# NL_Sheet1.net
KiCad netlist of a schematic drawn in Altium Designer
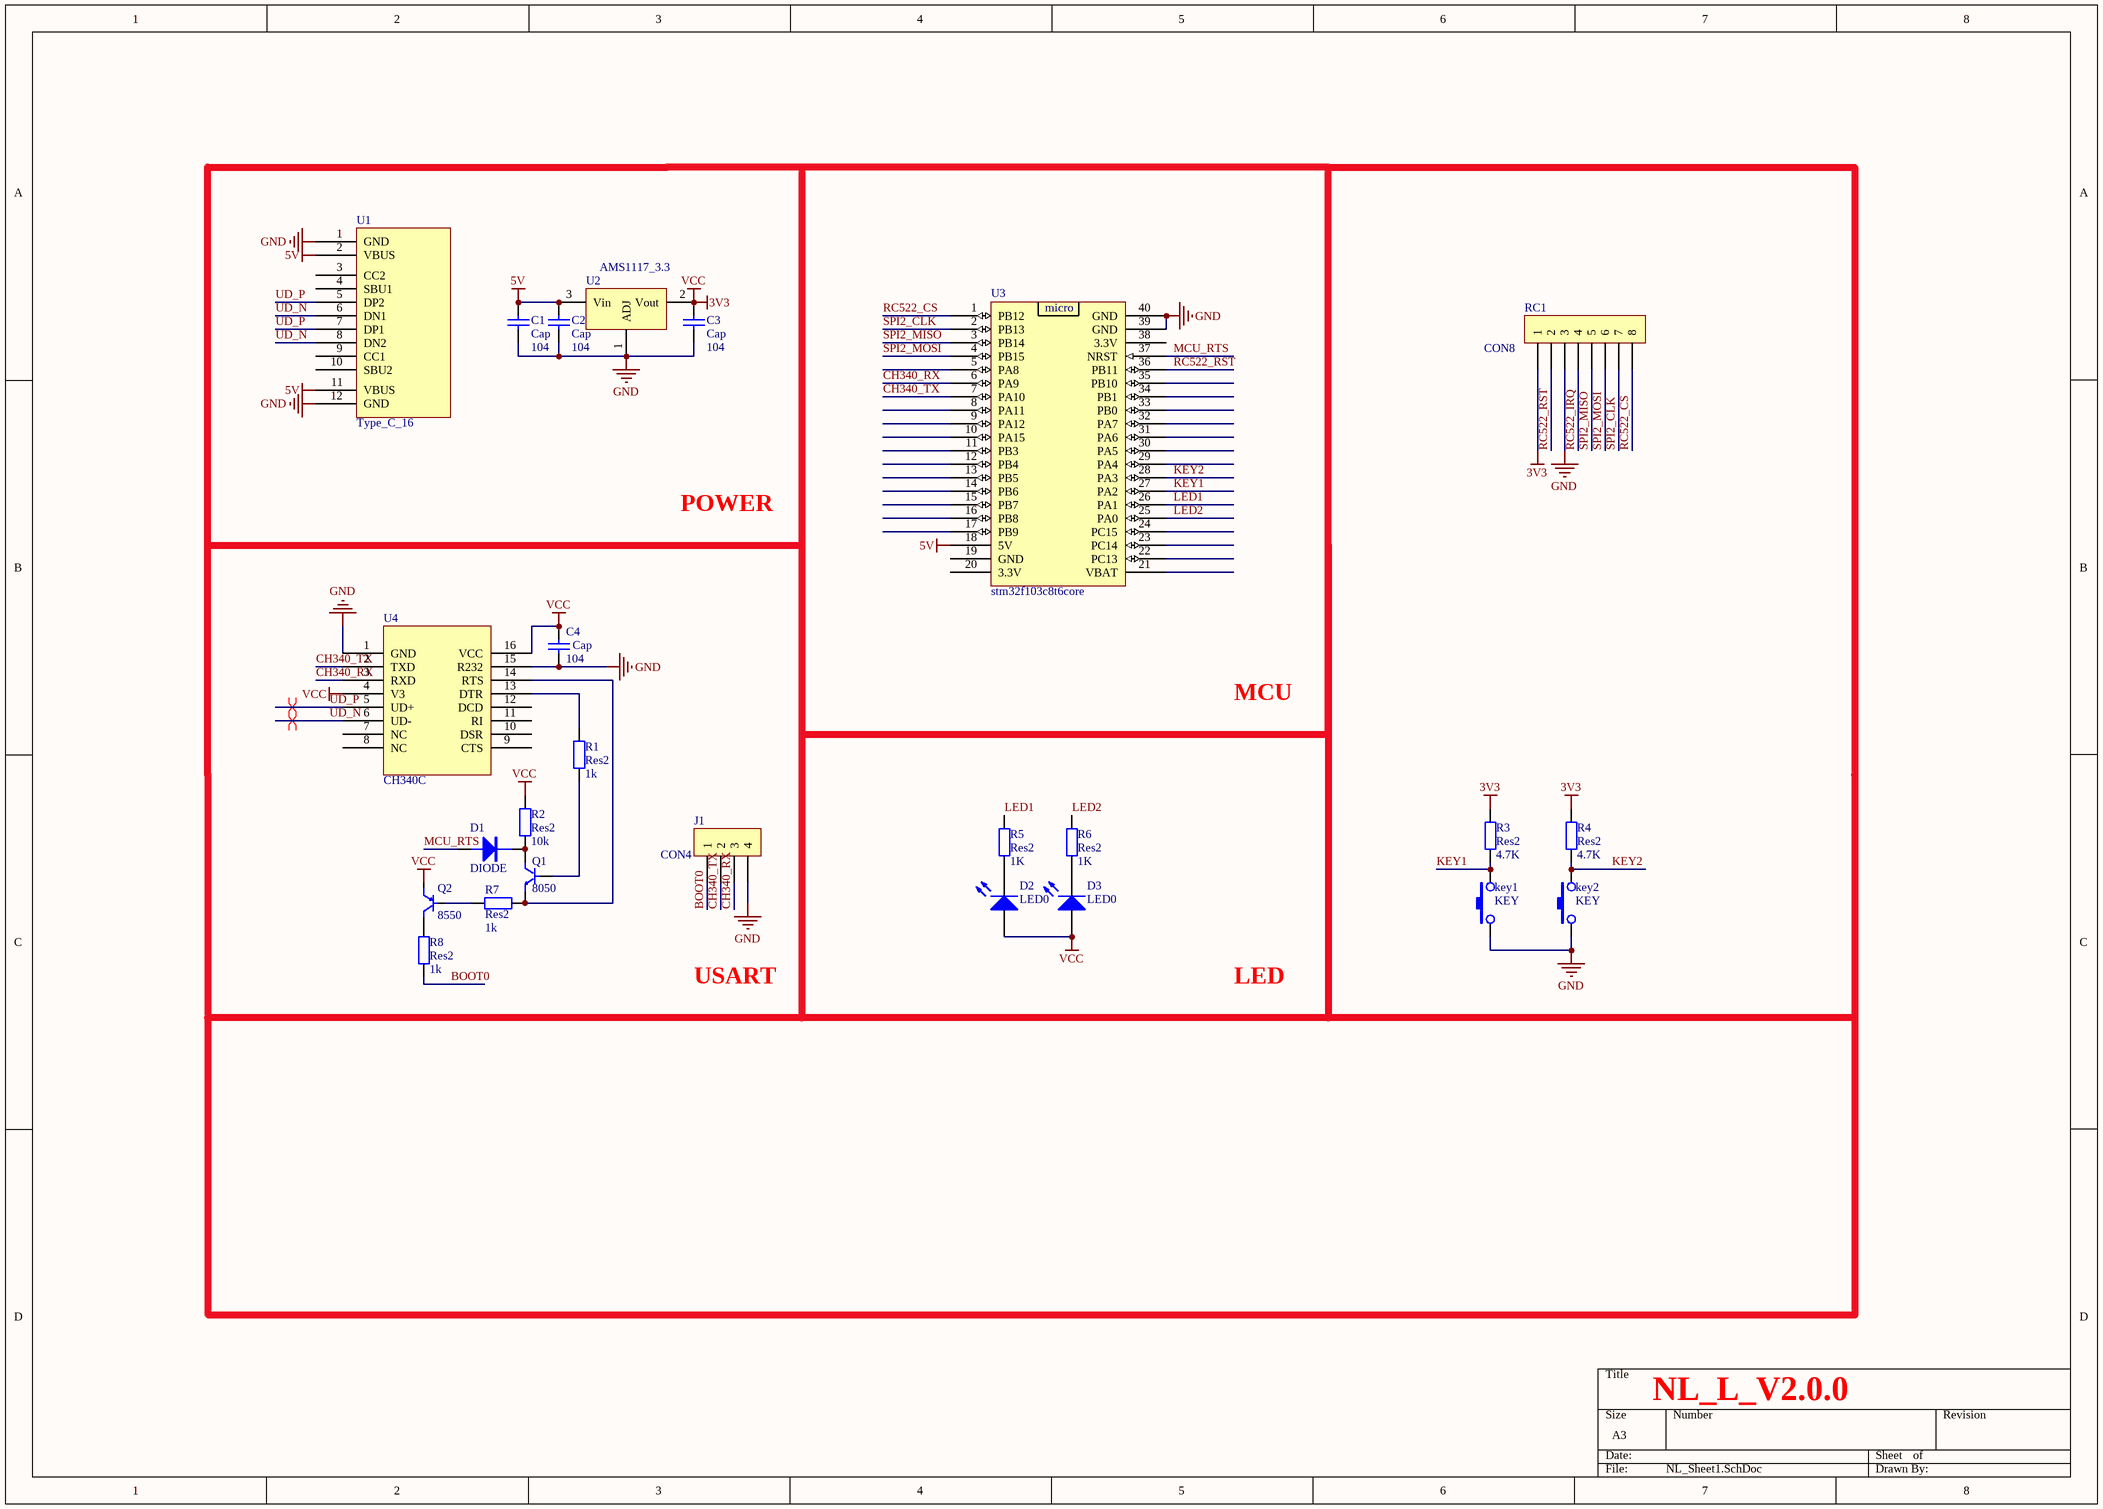
[diagram p0: NL_Sheet1.SchDoc]

(export (version "E")
  (design (tool "Eeschema 10.0.6"))
  (components
    (comp (ref "C1")
      (value "Cap")
      (footprint "0805")
      (description "Capacitor")
      (fields (field (name "ALTIUM_VALUE") "104") (field (name "PUBLISHER") "Altium Limited"))
      (libsource (lib "Miscellaneous Devices") (part "Cap"))
    )
    (comp (ref "C2")
      (value "Cap")
      (footprint "0805")
      (description "Capacitor")
      (fields (field (name "ALTIUM_VALUE") "104") (field (name "PUBLISHER") "Altium Limited"))
      (libsource (lib "Miscellaneous Devices") (part "Cap"))
    )
    (comp (ref "C3")
      (value "Cap")
      (footprint "0805")
      (description "Capacitor")
      (fields (field (name "ALTIUM_VALUE") "104") (field (name "PUBLISHER") "Altium Limited"))
      (libsource (lib "Miscellaneous Devices") (part "Cap"))
    )
    (comp (ref "C4")
      (value "Cap")
      (footprint "0805")
      (description "Capacitor")
      (fields (field (name "ALTIUM_VALUE") "104") (field (name "PUBLISHER") "Altium Limited"))
      (libsource (lib "Miscellaneous Devices") (part "Cap"))
    )
    (comp (ref "D1") (value "DIODE") (footprint "0805L") (libsource (lib "常用1") (part "DIODE")))
    (comp (ref "D2")
      (value "LED0")
      (footprint "0805")
      (description "Typical INFRARED GaAs LED")
      (fields (field (name "PUBLISHER") "Altium Limited"))
      (libsource (lib "Miscellaneous Devices") (part "LED0"))
    )
    (comp (ref "D3")
      (value "LED0")
      (footprint "0805")
      (description "Typical INFRARED GaAs LED")
      (fields (field (name "PUBLISHER") "Altium Limited"))
      (libsource (lib "Miscellaneous Devices") (part "LED0"))
    )
    (comp (ref "J1") (value "CON4") (footprint "SIP4") (libsource (lib "常用元件库") (part "CON4")))
    (comp (ref "key1") (value "KEY") (footprint "Key") (libsource (lib "常用元件库") (part "KEY")))
    (comp (ref "key2") (value "KEY") (footprint "Key") (libsource (lib "常用元件库") (part "KEY")))
    (comp (ref "Q1") (value "8050") (footprint "SOT23") (libsource (lib "NL_PCB_Project") (part "NPN")))
    (comp (ref "Q2") (value "8550") (footprint "SOT23") (libsource (lib "NL_PCB_Project") (part "PNP")))
    (comp (ref "R1")
      (value "Res2")
      (footprint "0805")
      (description "Resistor")
      (fields (field (name "ALTIUM_VALUE") "1k") (field (name "PUBLISHER") "Altium Limited"))
      (libsource (lib "Miscellaneous Devices") (part "Res2"))
    )
    (comp (ref "R2")
      (value "Res2")
      (footprint "0805")
      (description "Resistor")
      (fields (field (name "ALTIUM_VALUE") "10k") (field (name "PUBLISHER") "Altium Limited"))
      (libsource (lib "Miscellaneous Devices") (part "Res2"))
    )
    (comp (ref "R3")
      (value "Res2")
      (footprint "0805")
      (description "Resistor")
      (fields (field (name "ALTIUM_VALUE") "4.7K") (field (name "PUBLISHER") "Altium Limited"))
      (libsource (lib "Miscellaneous Devices") (part "Res2"))
    )
    (comp (ref "R4")
      (value "Res2")
      (footprint "0805")
      (description "Resistor")
      (fields (field (name "ALTIUM_VALUE") "4.7K") (field (name "PUBLISHER") "Altium Limited"))
      (libsource (lib "") (part "Res2_1"))
    )
    (comp (ref "R5")
      (value "Res2")
      (footprint "0805")
      (description "Resistor")
      (fields (field (name "ALTIUM_VALUE") "1K") (field (name "PUBLISHER") "Altium Limited"))
      (libsource (lib "") (part "Res2_1"))
    )
    (comp (ref "R6")
      (value "Res2")
      (footprint "0805")
      (description "Resistor")
      (fields (field (name "ALTIUM_VALUE") "1K") (field (name "PUBLISHER") "Altium Limited"))
      (libsource (lib "") (part "Res2_1"))
    )
    (comp (ref "R7")
      (value "Res2")
      (footprint "0805")
      (description "Resistor")
      (fields (field (name "ALTIUM_VALUE") "1k") (field (name "PUBLISHER") "Altium Limited"))
      (libsource (lib "") (part "Res2_2"))
    )
    (comp (ref "R8")
      (value "Res2")
      (footprint "0805")
      (description "Resistor")
      (fields (field (name "ALTIUM_VALUE") "1k") (field (name "PUBLISHER") "Altium Limited"))
      (libsource (lib "") (part "Res2_1"))
    )
    (comp (ref "RC1") (value "CON8") (footprint "RC522_SIP8") (libsource (lib "常用元件库") (part "CON8")))
    (comp (ref "U1") (value "Type_C_16") (footprint "Type_C16") (libsource (lib "常用1") (part "Type_C_16")))
    (comp (ref "U2")
      (value "AMS1117_3.3")
      (footprint "SOT-223")
      (description "3-Terminal Adjustable Positive Voltage Regulator")
      (libsource (lib "稳压器件") (part "LM317"))
    )
    (comp (ref "U3")
      (value "stm32f103c8t6core")
      (footprint "stm32f103DIP40")
      (libsource (lib "常用元件库") (part "stm32f103c8t6core"))
    )
    (comp (ref "U4") (value "CH340C") (footprint "SOP16") (libsource (lib "常用1") (part "CH340C")))
  )
  (nets
    (net (code "1") (name "/BOOT0") (class "Default")
      (node (ref "J1") (pin "1") (pinfunction "1_1") (pintype "passive"))
      (node (ref "R8") (pin "1") (pinfunction "1_1") (pintype "passive"))
    )
    (net (code "2") (name "/CH340_RX") (class "Default")
      (node (ref "J1") (pin "3") (pinfunction "3_3") (pintype "passive"))
      (node (ref "U3") (pin "6") (pinfunction "PA9_6") (pintype "bidirectional"))
      (node (ref "U4") (pin "3") (pinfunction "RXD_3") (pintype "passive"))
    )
    (net (code "3") (name "/CH340_TX") (class "Default")
      (node (ref "J1") (pin "2") (pinfunction "2_2") (pintype "passive"))
      (node (ref "U3") (pin "7") (pinfunction "PA10_7") (pintype "bidirectional"))
      (node (ref "U4") (pin "2") (pinfunction "TXD_2") (pintype "passive"))
    )
    (net (code "4") (name "/KEY1") (class "Default")
      (node (ref "R3") (pin "2") (pinfunction "2_2") (pintype "passive"))
      (node (ref "U3") (pin "27") (pinfunction "PA2_27") (pintype "bidirectional"))
      (node (ref "key1") (pin "2") (pinfunction "2_2") (pintype "passive"))
    )
    (net (code "5") (name "/KEY2") (class "Default")
      (node (ref "R4") (pin "1") (pinfunction "1_1") (pintype "passive"))
      (node (ref "U3") (pin "28") (pinfunction "PA3_28") (pintype "bidirectional"))
      (node (ref "key2") (pin "2") (pinfunction "2_2") (pintype "passive"))
    )
    (net (code "6") (name "/LED1") (class "Default")
      (node (ref "R5") (pin "2") (pinfunction "2_2") (pintype "passive"))
      (node (ref "U3") (pin "26") (pinfunction "PA1_26") (pintype "bidirectional"))
    )
    (net (code "7") (name "/LED2") (class "Default")
      (node (ref "R6") (pin "2") (pinfunction "2_2") (pintype "passive"))
      (node (ref "U3") (pin "25") (pinfunction "PA0_25") (pintype "bidirectional"))
    )
    (net (code "8") (name "/MCU_RTS") (class "Default")
      (node (ref "D1") (pin "1") (pintype "passive"))
      (node (ref "U3") (pin "37") (pinfunction "NRST_37") (pintype "input"))
    )
    (net (code "9") (name "/RC522_CS") (class "Default")
      (node (ref "RC1") (pin "8") (pinfunction "8_8") (pintype "passive"))
      (node (ref "U3") (pin "1") (pinfunction "PB12_1") (pintype "bidirectional"))
    )
    (net (code "10") (name "/RC522_IRQ") (class "Default")
      (node (ref "RC1") (pin "4") (pinfunction "4_4") (pintype "passive"))
    )
    (net (code "11") (name "/RC522_RST") (class "Default")
      (node (ref "RC1") (pin "2") (pinfunction "2_2") (pintype "passive"))
      (node (ref "U3") (pin "36") (pinfunction "PB11_36") (pintype "bidirectional"))
    )
    (net (code "12") (name "/SPI2_CLK") (class "Default")
      (node (ref "RC1") (pin "7") (pinfunction "7_7") (pintype "passive"))
      (node (ref "U3") (pin "2") (pinfunction "PB13_2") (pintype "bidirectional"))
    )
    (net (code "13") (name "/SPI2_MISO") (class "Default")
      (node (ref "RC1") (pin "5") (pinfunction "5_5") (pintype "passive"))
      (node (ref "U3") (pin "3") (pinfunction "PB14_3") (pintype "bidirectional"))
    )
    (net (code "14") (name "/SPI2_MOSI") (class "Default")
      (node (ref "RC1") (pin "6") (pinfunction "6_6") (pintype "passive"))
      (node (ref "U3") (pin "4") (pinfunction "PB15_4") (pintype "bidirectional"))
    )
    (net (code "15") (name "/UD_N") (class "Default")
      (node (ref "U1") (pin "6") (pinfunction "DN1_6") (pintype "passive"))
      (node (ref "U1") (pin "8") (pinfunction "DN2_8") (pintype "passive"))
      (node (ref "U4") (pin "6") (pinfunction "UD-_6") (pintype "passive"))
    )
    (net (code "16") (name "/UD_P") (class "Default")
      (node (ref "U1") (pin "5") (pinfunction "DP2_5") (pintype "passive"))
      (node (ref "U1") (pin "7") (pinfunction "DP1_7") (pintype "passive"))
      (node (ref "U4") (pin "5") (pinfunction "UD+_5") (pintype "passive"))
    )
    (net (code "17") (name "3V3") (class "Default")
      (node (ref "C3") (pin "2") (pinfunction "2_2") (pintype "passive"))
      (node (ref "C4") (pin "2") (pinfunction "2_2") (pintype "passive"))
      (node (ref "D2") (pin "1") (pinfunction "A_1") (pintype "passive"))
      (node (ref "D3") (pin "1") (pinfunction "A_1") (pintype "passive"))
      (node (ref "Q2") (pin "e") (pinfunction "e_e") (pintype "passive"))
      (node (ref "R2") (pin "1") (pinfunction "1_1") (pintype "passive"))
      (node (ref "R3") (pin "1") (pinfunction "1_1") (pintype "passive"))
      (node (ref "R4") (pin "2") (pinfunction "2_2") (pintype "passive"))
      (node (ref "RC1") (pin "1") (pinfunction "1_1") (pintype "passive"))
      (node (ref "U2") (pin "2") (pinfunction "Vout_2") (pintype "passive"))
      (node (ref "U4") (pin "16") (pinfunction "VCC_16") (pintype "passive"))
      (node (ref "U4") (pin "4") (pinfunction "V3_4") (pintype "passive"))
    )
    (net (code "18") (name "5V") (class "Default")
      (node (ref "C1") (pin "2") (pinfunction "2_2") (pintype "passive"))
      (node (ref "C2") (pin "2") (pinfunction "2_2") (pintype "passive"))
      (node (ref "U1") (pin "11") (pinfunction "VBUS_11") (pintype "passive"))
      (node (ref "U1") (pin "2") (pinfunction "VBUS_2") (pintype "passive"))
      (node (ref "U2") (pin "3") (pinfunction "Vin_3") (pintype "passive"))
      (node (ref "U3") (pin "18") (pinfunction "5V_18") (pintype "power_in"))
    )
    (net (code "19") (name "GND") (class "Default")
      (node (ref "C1") (pin "1") (pinfunction "1_1") (pintype "passive"))
      (node (ref "C2") (pin "1") (pinfunction "1_1") (pintype "passive"))
      (node (ref "C3") (pin "1") (pinfunction "1_1") (pintype "passive"))
      (node (ref "C4") (pin "1") (pinfunction "1_1") (pintype "passive"))
      (node (ref "J1") (pin "4") (pinfunction "4_4") (pintype "passive"))
      (node (ref "RC1") (pin "3") (pinfunction "3_3") (pintype "passive"))
      (node (ref "U1") (pin "1") (pinfunction "GND_1") (pintype "passive"))
      (node (ref "U1") (pin "12") (pinfunction "GND_12") (pintype "passive"))
      (node (ref "U2") (pin "1") (pinfunction "ADJ_1") (pintype "passive"))
      (node (ref "U3") (pin "39") (pinfunction "GND_39") (pintype "power_in"))
      (node (ref "U3") (pin "40") (pinfunction "GND_40") (pintype "power_in"))
      (node (ref "U4") (pin "1") (pinfunction "GND_1") (pintype "passive"))
      (node (ref "U4") (pin "15") (pinfunction "R232_15") (pintype "passive"))
      (node (ref "key1") (pin "1") (pinfunction "1_1") (pintype "passive"))
      (node (ref "key2") (pin "1") (pinfunction "1_1") (pintype "passive"))
    )
    (net (code "20") (name "Net-(D1-Pad2)") (class "Default")
      (node (ref "D1") (pin "2") (pintype "passive"))
      (node (ref "Q1") (pin "c") (pinfunction "c_c") (pintype "passive"))
      (node (ref "R2") (pin "2") (pinfunction "2_2") (pintype "passive"))
    )
    (net (code "21") (name "Net-(D2-K)") (class "Default")
      (node (ref "D2") (pin "2") (pinfunction "K_2") (pintype "passive"))
      (node (ref "R5") (pin "1") (pinfunction "1_1") (pintype "passive"))
    )
    (net (code "22") (name "Net-(D3-K)") (class "Default")
      (node (ref "D3") (pin "2") (pinfunction "K_2") (pintype "passive"))
      (node (ref "R6") (pin "1") (pinfunction "1_1") (pintype "passive"))
    )
    (net (code "23") (name "Net-(Q1-Padb)") (class "Default")
      (node (ref "Q1") (pin "b") (pinfunction "b_b") (pintype "passive"))
      (node (ref "R1") (pin "2") (pinfunction "2_2") (pintype "passive"))
    )
    (net (code "24") (name "Net-(Q2-Padb)") (class "Default")
      (node (ref "Q2") (pin "b") (pinfunction "b_b") (pintype "passive"))
      (node (ref "R7") (pin "1") (pinfunction "1_1") (pintype "passive"))
    )
    (net (code "25") (name "Net-(Q2-Padc)") (class "Default")
      (node (ref "Q2") (pin "c") (pinfunction "c_c") (pintype "passive"))
      (node (ref "R8") (pin "2") (pinfunction "2_2") (pintype "passive"))
    )
    (net (code "26") (name "Net-(U4-DTR)") (class "Default")
      (node (ref "R1") (pin "1") (pinfunction "1_1") (pintype "passive"))
      (node (ref "U4") (pin "13") (pinfunction "DTR_13") (pintype "passive"))
    )
    (net (code "27") (name "Net-(U4-RTS)") (class "Default")
      (node (ref "Q1") (pin "e") (pinfunction "e_e") (pintype "passive"))
      (node (ref "R7") (pin "2") (pinfunction "2_2") (pintype "passive"))
      (node (ref "U4") (pin "14") (pinfunction "RTS_14") (pintype "passive"))
    )
    (net (code "28") (name "unconnected-(U1-CC1-Pad9)") (class "Default")
      (node (ref "U1") (pin "9") (pinfunction "CC1_9") (pintype "passive"))
    )
    (net (code "29") (name "unconnected-(U1-CC2-Pad3)") (class "Default")
      (node (ref "U1") (pin "3") (pinfunction "CC2_3") (pintype "passive"))
    )
    (net (code "30") (name "unconnected-(U1-SBU1-Pad4)") (class "Default")
      (node (ref "U1") (pin "4") (pinfunction "SBU1_4") (pintype "passive"))
    )
    (net (code "31") (name "unconnected-(U1-SBU2-Pad10)") (class "Default")
      (node (ref "U1") (pin "10") (pinfunction "SBU2_10") (pintype "passive"))
    )
    (net (code "32") (name "unconnected-(U3-3.3V-Pad20)") (class "Default")
      (node (ref "U3") (pin "20") (pinfunction "3.3V_20") (pintype "power_in"))
    )
    (net (code "33") (name "unconnected-(U3-3.3V-Pad38)") (class "Default")
      (node (ref "U3") (pin "38") (pinfunction "3.3V_38") (pintype "power_in"))
    )
    (net (code "34") (name "unconnected-(U3-GND-Pad19)") (class "Default")
      (node (ref "U3") (pin "19") (pinfunction "GND_19") (pintype "power_in"))
    )
    (net (code "35") (name "unconnected-(U3-PA4-Pad29)") (class "Default")
      (node (ref "U3") (pin "29") (pinfunction "PA4_29") (pintype "bidirectional"))
    )
    (net (code "36") (name "unconnected-(U3-PA5-Pad30)") (class "Default")
      (node (ref "U3") (pin "30") (pinfunction "PA5_30") (pintype "bidirectional"))
    )
    (net (code "37") (name "unconnected-(U3-PA6-Pad31)") (class "Default")
      (node (ref "U3") (pin "31") (pinfunction "PA6_31") (pintype "bidirectional"))
    )
    (net (code "38") (name "unconnected-(U3-PA7-Pad32)") (class "Default")
      (node (ref "U3") (pin "32") (pinfunction "PA7_32") (pintype "bidirectional"))
    )
    (net (code "39") (name "unconnected-(U3-PA8-Pad5)") (class "Default")
      (node (ref "U3") (pin "5") (pinfunction "PA8_5") (pintype "bidirectional"))
    )
    (net (code "40") (name "unconnected-(U3-PA11-Pad8)") (class "Default")
      (node (ref "U3") (pin "8") (pinfunction "PA11_8") (pintype "bidirectional"))
    )
    (net (code "41") (name "unconnected-(U3-PA12-Pad9)") (class "Default")
      (node (ref "U3") (pin "9") (pinfunction "PA12_9") (pintype "bidirectional"))
    )
    (net (code "42") (name "unconnected-(U3-PA15-Pad10)") (class "Default")
      (node (ref "U3") (pin "10") (pinfunction "PA15_10") (pintype "bidirectional"))
    )
    (net (code "43") (name "unconnected-(U3-PB0-Pad33)") (class "Default")
      (node (ref "U3") (pin "33") (pinfunction "PB0_33") (pintype "bidirectional"))
    )
    (net (code "44") (name "unconnected-(U3-PB1-Pad34)") (class "Default")
      (node (ref "U3") (pin "34") (pinfunction "PB1_34") (pintype "bidirectional"))
    )
    (net (code "45") (name "unconnected-(U3-PB3-Pad11)") (class "Default")
      (node (ref "U3") (pin "11") (pinfunction "PB3_11") (pintype "bidirectional"))
    )
    (net (code "46") (name "unconnected-(U3-PB4-Pad12)") (class "Default")
      (node (ref "U3") (pin "12") (pinfunction "PB4_12") (pintype "bidirectional"))
    )
    (net (code "47") (name "unconnected-(U3-PB5-Pad13)") (class "Default")
      (node (ref "U3") (pin "13") (pinfunction "PB5_13") (pintype "bidirectional"))
    )
    (net (code "48") (name "unconnected-(U3-PB6-Pad14)") (class "Default")
      (node (ref "U3") (pin "14") (pinfunction "PB6_14") (pintype "bidirectional"))
    )
    (net (code "49") (name "unconnected-(U3-PB7-Pad15)") (class "Default")
      (node (ref "U3") (pin "15") (pinfunction "PB7_15") (pintype "bidirectional"))
    )
    (net (code "50") (name "unconnected-(U3-PB8-Pad16)") (class "Default")
      (node (ref "U3") (pin "16") (pinfunction "PB8_16") (pintype "bidirectional"))
    )
    (net (code "51") (name "unconnected-(U3-PB9-Pad17)") (class "Default")
      (node (ref "U3") (pin "17") (pinfunction "PB9_17") (pintype "bidirectional"))
    )
    (net (code "52") (name "unconnected-(U3-PB10-Pad35)") (class "Default")
      (node (ref "U3") (pin "35") (pinfunction "PB10_35") (pintype "bidirectional"))
    )
    (net (code "53") (name "unconnected-(U3-PC13-Pad22)") (class "Default")
      (node (ref "U3") (pin "22") (pinfunction "PC13_22") (pintype "bidirectional"))
    )
    (net (code "54") (name "unconnected-(U3-PC14-Pad23)") (class "Default")
      (node (ref "U3") (pin "23") (pinfunction "PC14_23") (pintype "bidirectional"))
    )
    (net (code "55") (name "unconnected-(U3-PC15-Pad24)") (class "Default")
      (node (ref "U3") (pin "24") (pinfunction "PC15_24") (pintype "bidirectional"))
    )
    (net (code "56") (name "unconnected-(U3-VBAT-Pad21)") (class "Default")
      (node (ref "U3") (pin "21") (pinfunction "VBAT_21") (pintype "power_in"))
    )
    (net (code "57") (name "unconnected-(U4-CTS-Pad9)") (class "Default")
      (node (ref "U4") (pin "9") (pinfunction "CTS_9") (pintype "passive"))
    )
    (net (code "58") (name "unconnected-(U4-DCD-Pad12)") (class "Default")
      (node (ref "U4") (pin "12") (pinfunction "DCD_12") (pintype "passive"))
    )
    (net (code "59") (name "unconnected-(U4-DSR-Pad10)") (class "Default")
      (node (ref "U4") (pin "10") (pinfunction "DSR_10") (pintype "passive"))
    )
    (net (code "60") (name "unconnected-(U4-NC-Pad7)") (class "Default")
      (node (ref "U4") (pin "7") (pinfunction "NC_7") (pintype "passive"))
    )
    (net (code "61") (name "unconnected-(U4-NC-Pad8)") (class "Default")
      (node (ref "U4") (pin "8") (pinfunction "NC_8") (pintype "passive"))
    )
    (net (code "62") (name "unconnected-(U4-RI-Pad11)") (class "Default")
      (node (ref "U4") (pin "11") (pinfunction "RI_11") (pintype "passive"))
    )
  )
)
